# settings2.net
KiCad netlist of a schematic drawn in EAGLE
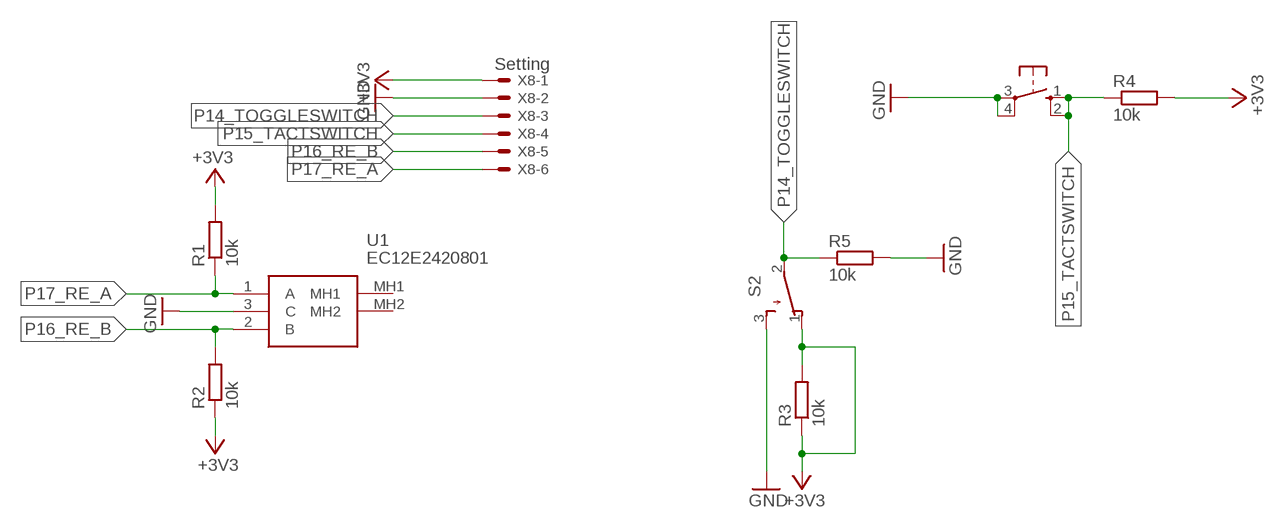
[diagram p0: schematic, sheet 1]

(export (version "E")
  (design (tool "Eeschema 10.0.6"))
  (components
    (comp (ref "R1")
      (value "10k")
      (footprint "eagle-import:R0603")
      (libsource (lib "eagle-import") (part "R-EU_R0603"))
    )
    (comp (ref "R2")
      (value "10k")
      (footprint "eagle-import:R0603")
      (libsource (lib "eagle-import") (part "R-EU_R0603"))
    )
    (comp (ref "R3")
      (value "10k")
      (footprint "eagle-import:R0603")
      (libsource (lib "eagle-import") (part "R-EU_R0603"))
    )
    (comp (ref "R4")
      (value "10k")
      (footprint "eagle-import:R0603")
      (libsource (lib "eagle-import") (part "R-EU_R0603"))
    )
    (comp (ref "R5")
      (value "10k")
      (footprint "eagle-import:R0603")
      (libsource (lib "eagle-import") (part "R-EU_R0603"))
    )
    (comp (ref "S1")
      (value "40-XX")
      (footprint "eagle-import:B3F-40XX")
      (fields (field (name "MF") "OMRON COMPONENTS USA") (field (name "MPN") "B3F-4000"))
      (libsource (lib "eagle-import") (part "40-XX"))
    )
    (comp (ref "S2")
      (value "TL32PO")
      (footprint "eagle-import:TL3XPO")
      (libsource (lib "eagle-import") (part "TL32PO"))
    )
    (comp (ref "U1")
      (value "EC12E2420801")
      (footprint "eagle-import:EC12E2420801")
      (fields (field (name "RS_PART_NUMBER") "7295836"))
      (libsource (lib "eagle-import") (part "EC12E2420801"))
    )
    (comp (ref "X8")
      (value "Setting")
      (footprint "eagle-import:JST-XH-06-PACKAGE-ROUND-PAD")
      (libsource (lib "eagle-import") (part "JST-XH-06-PIN-ROUND-PAD"))
    )
  )
  (nets
    (net (code "1") (name "+3V3") (class "Default")
      (node (ref "R1") (pin "2") (pinfunction "2_2") (pintype "passive"))
      (node (ref "R2") (pin "1") (pinfunction "1_1") (pintype "passive"))
      (node (ref "R3") (pin "1") (pinfunction "1_1") (pintype "passive"))
      (node (ref "R3") (pin "2") (pinfunction "2_2") (pintype "passive"))
      (node (ref "R4") (pin "2") (pinfunction "2_2") (pintype "passive"))
      (node (ref "S2") (pin "1") (pinfunction "O_1") (pintype "passive"))
      (node (ref "X8") (pin "1") (pinfunction "S_1") (pintype "passive"))
    )
    (net (code "2") (name "GND") (class "Default")
      (node (ref "R5") (pin "2") (pinfunction "2_2") (pintype "passive"))
      (node (ref "S1") (pin "3") (pinfunction "P_3") (pintype "passive"))
      (node (ref "S1") (pin "4") (pinfunction "P1_4") (pintype "passive"))
      (node (ref "S2") (pin "3") (pinfunction "S_3") (pintype "passive"))
      (node (ref "U1") (pin "3") (pinfunction "C_3") (pintype "bidirectional"))
      (node (ref "X8") (pin "2") (pinfunction "S_2") (pintype "passive"))
    )
    (net (code "3") (name "P14_TOGGLESWITCH") (class "Default")
      (node (ref "R5") (pin "1") (pinfunction "1_1") (pintype "passive"))
      (node (ref "S2") (pin "2") (pinfunction "P_2") (pintype "passive"))
      (node (ref "X8") (pin "3") (pinfunction "S_3") (pintype "passive"))
    )
    (net (code "4") (name "P15_TACTSWITCH") (class "Default")
      (node (ref "R4") (pin "1") (pinfunction "1_1") (pintype "passive"))
      (node (ref "S1") (pin "1") (pinfunction "S_1") (pintype "passive"))
      (node (ref "S1") (pin "2") (pinfunction "S1_2") (pintype "passive"))
      (node (ref "X8") (pin "4") (pinfunction "S_4") (pintype "passive"))
    )
    (net (code "5") (name "P16_RE_B") (class "Default")
      (node (ref "R2") (pin "2") (pinfunction "2_2") (pintype "passive"))
      (node (ref "U1") (pin "2") (pinfunction "B_2") (pintype "bidirectional"))
      (node (ref "X8") (pin "5") (pinfunction "S_5") (pintype "passive"))
    )
    (net (code "6") (name "P17_RE_A") (class "Default")
      (node (ref "R1") (pin "1") (pinfunction "1_1") (pintype "passive"))
      (node (ref "U1") (pin "1") (pinfunction "A_1") (pintype "bidirectional"))
      (node (ref "X8") (pin "6") (pinfunction "S_6") (pintype "passive"))
    )
    (net (code "7") (name "unconnected-(U1-PadMH1)") (class "Default")
      (node (ref "U1") (pin "MH1") (pinfunction "MH1_MH1") (pintype "bidirectional"))
    )
    (net (code "8") (name "unconnected-(U1-PadMH2)") (class "Default")
      (node (ref "U1") (pin "MH2") (pinfunction "MH2_MH2") (pintype "bidirectional"))
    )
  )
)
